# SDuino_ultramicroOLED_radio4.net
KiCad netlist of a schematic drawn in EAGLE
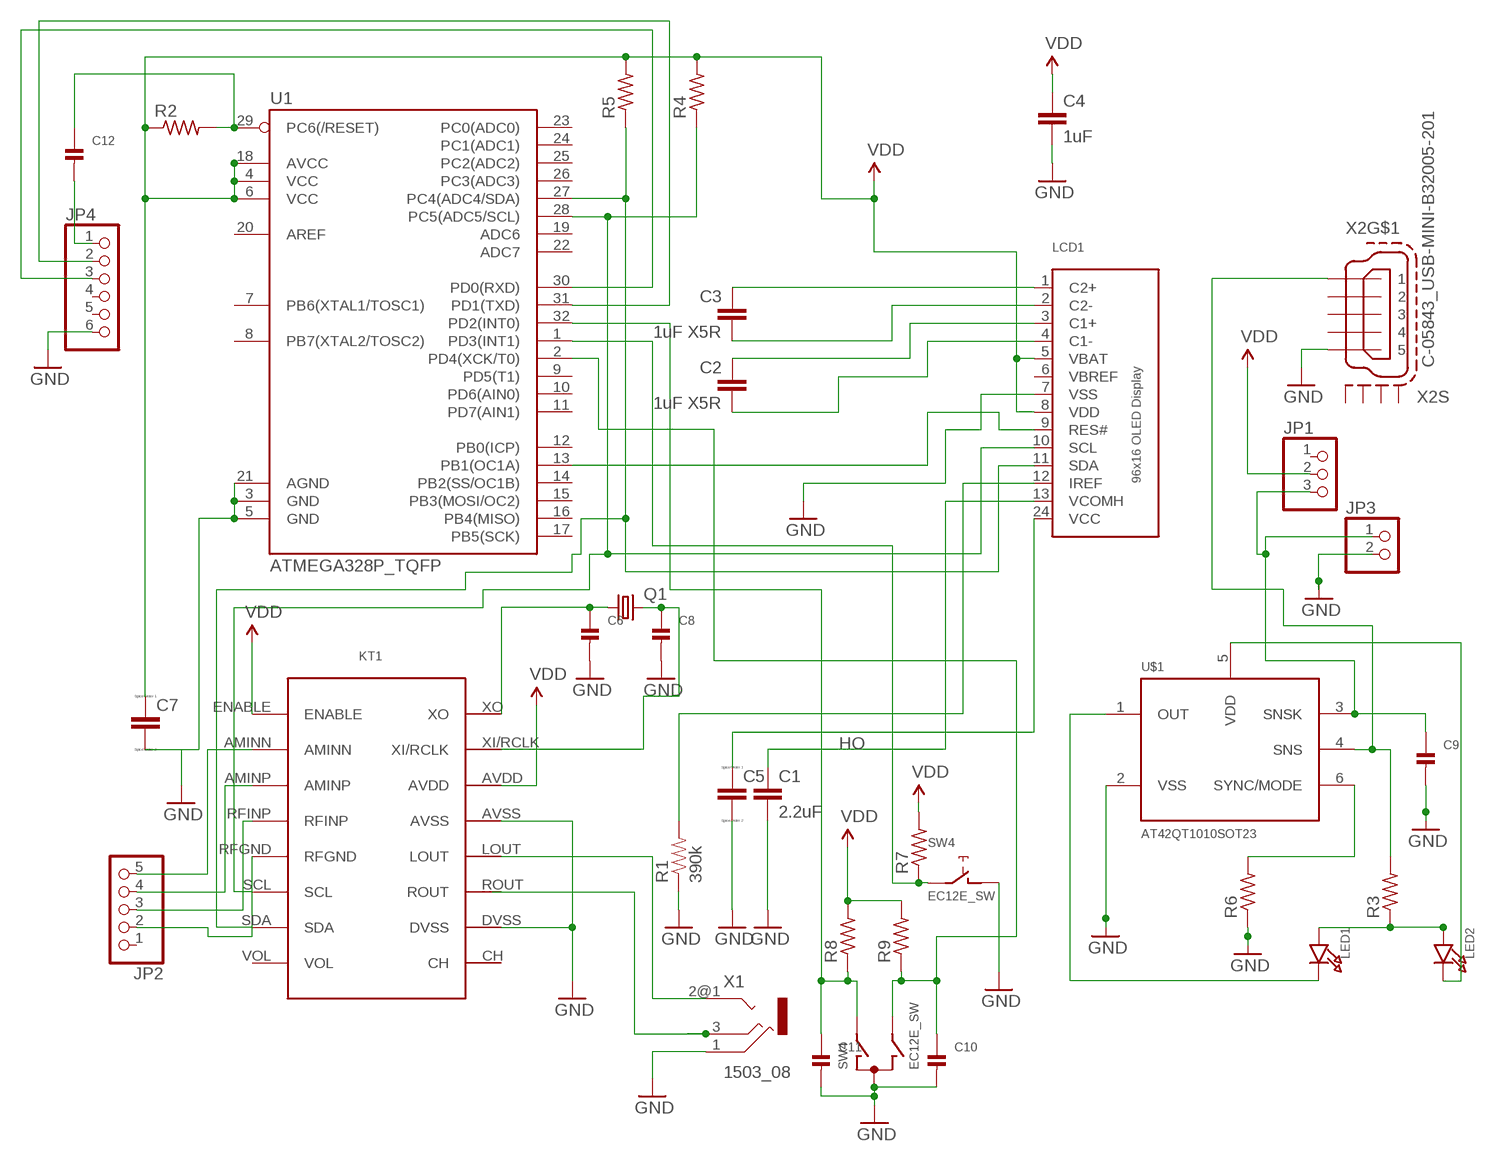
[diagram p0: schematic, sheet 1]

(export (version "E")
  (design (tool "Eeschema 10.0.6"))
  (components
    (comp (ref "C1")
      (value "2.2uF")
      (footprint "eagle-import:0805")
      (libsource (lib "eagle-import") (part "CAP0805"))
    )
    (comp (ref "C2")
      (value "1uF X5R")
      (footprint "eagle-import:0805")
      (libsource (lib "eagle-import") (part "CAP0805"))
    )
    (comp (ref "C3")
      (value "1uF X5R")
      (footprint "eagle-import:0805")
      (libsource (lib "eagle-import") (part "CAP0805"))
    )
    (comp (ref "C4")
      (value "1uF")
      (footprint "eagle-import:0603-CAP")
      (libsource (lib "eagle-import") (part "CAP0603-CAP"))
    )
    (comp (ref "C5")
      (value "CC0603")
      (footprint "eagle-import:C0603")
      (libsource (lib "eagle-import") (part "CC0603"))
    )
    (comp (ref "C6")
      (value "CAP_CERAMIC0603")
      (footprint "eagle-import:0603")
      (libsource (lib "eagle-import") (part "CAP_CERAMIC0603"))
    )
    (comp (ref "C7")
      (value "CC0603")
      (footprint "eagle-import:C0603")
      (libsource (lib "eagle-import") (part "CC0603"))
    )
    (comp (ref "C8")
      (value "CAP_CERAMIC0603")
      (footprint "eagle-import:0603")
      (libsource (lib "eagle-import") (part "CAP_CERAMIC0603"))
    )
    (comp (ref "C9")
      (value "CAP_CERAMIC0603")
      (footprint "eagle-import:0603")
      (libsource (lib "eagle-import") (part "CAP_CERAMIC0603"))
    )
    (comp (ref "C10")
      (value "CAP_CERAMIC0603")
      (footprint "eagle-import:0603")
      (libsource (lib "eagle-import") (part "CAP_CERAMIC0603"))
    )
    (comp (ref "C11")
      (value "CAP_CERAMIC0603")
      (footprint "eagle-import:0603")
      (libsource (lib "eagle-import") (part "CAP_CERAMIC0603"))
    )
    (comp (ref "C12")
      (value "CAP_CERAMIC0603")
      (footprint "eagle-import:0603")
      (libsource (lib "eagle-import") (part "CAP_CERAMIC0603"))
    )
    (comp (ref "JP1")
      (value "HEADER-1X3")
      (footprint "eagle-import:1X03_OVAL")
      (libsource (lib "eagle-import") (part "HEADER-1X3"))
    )
    (comp (ref "JP2")
      (value "HEADER-1X5")
      (footprint "eagle-import:1X05_OVAL")
      (libsource (lib "eagle-import") (part "HEADER-1X5"))
    )
    (comp (ref "JP3")
      (value "HEADER-1X2")
      (footprint "eagle-import:1X02_OVAL")
      (libsource (lib "eagle-import") (part "HEADER-1X2"))
    )
    (comp (ref "JP4")
      (value "HEADER-1X6")
      (footprint "eagle-import:1X06_OVAL")
      (libsource (lib "eagle-import") (part "HEADER-1X6"))
    )
    (comp (ref "KT1")
      (value "KT0915")
      (footprint "eagle-import:KT0915")
      (libsource (lib "eagle-import") (part "KT0915"))
    )
    (comp (ref "LCD1")
      (value "DISP_OLED_UG-9616GLBBG02")
      (footprint "eagle-import:UG-9616GLBBG02_0.65MM_WRAPAROUND")
      (libsource (lib "eagle-import") (part "DISP_OLED_UG-9616GLBBG02"))
    )
    (comp (ref "LED1")
      (value "LED0603")
      (footprint "eagle-import:CHIPLED_0603")
      (libsource (lib "eagle-import") (part "LED0603"))
    )
    (comp (ref "LED2")
      (value "LED0603")
      (footprint "eagle-import:CHIPLED_0603")
      (libsource (lib "eagle-import") (part "LED0603"))
    )
    (comp (ref "Q1")
      (value "CRYSTALTC26V")
      (footprint "eagle-import:TC26V")
      (libsource (lib "eagle-import") (part "CRYSTALTC26V"))
    )
    (comp (ref "R1")
      (value "390k")
      (footprint "eagle-import:0603-RES")
      (libsource (lib "eagle-import") (part "RESISTOR0603-RES"))
    )
    (comp (ref "R2")
      (value "R-US_R0603")
      (footprint "eagle-import:R0603")
      (libsource (lib "eagle-import") (part "R-US_R0603"))
    )
    (comp (ref "R3")
      (value "R-US_R0603")
      (footprint "eagle-import:R0603")
      (libsource (lib "eagle-import") (part "R-US_R0603"))
    )
    (comp (ref "R4")
      (value "R-US_R0603")
      (footprint "eagle-import:R0603")
      (libsource (lib "eagle-import") (part "R-US_R0603"))
    )
    (comp (ref "R5")
      (value "R-US_R0603")
      (footprint "eagle-import:R0603")
      (libsource (lib "eagle-import") (part "R-US_R0603"))
    )
    (comp (ref "R6")
      (value "R-US_R0603")
      (footprint "eagle-import:R0603")
      (libsource (lib "eagle-import") (part "R-US_R0603"))
    )
    (comp (ref "R7")
      (value "R-US_R0603")
      (footprint "eagle-import:R0603")
      (libsource (lib "eagle-import") (part "R-US_R0603"))
    )
    (comp (ref "R8")
      (value "R-US_R0603")
      (footprint "eagle-import:R0603")
      (libsource (lib "eagle-import") (part "R-US_R0603"))
    )
    (comp (ref "R9")
      (value "R-US_R0603")
      (footprint "eagle-import:R0603")
      (libsource (lib "eagle-import") (part "R-US_R0603"))
    )
    (comp (ref "SW4")
      (value "EC12E_SW")
      (footprint "eagle-import:ALPS_EC12E_SW")
      (fields (field (name "MPN") "EC12E2424407"))
      (libsource (lib "eagle-import") (part "EC12E_SW"))
    )
    (comp (ref "U$1")
      (value "AT42QT1010SOT23")
      (footprint "eagle-import:SOT23-6")
      (libsource (lib "eagle-import") (part "AT42QT1010SOT23"))
    )
    (comp (ref "U1")
      (value "ATMEGA328P_TQFP")
      (footprint "eagle-import:TQFP32-08")
      (libsource (lib "eagle-import") (part "ATMEGA328P_TQFP"))
    )
    (comp (ref "X1")
      (value "1503_08")
      (footprint "eagle-import:1503_08")
      (libsource (lib "eagle-import") (part "1503_?08"))
    )
    (comp (ref "X2")
      (value "C-05843_USB-MINI-B32005-201")
      (footprint "eagle-import:32005-201")
      (libsource (lib "eagle-import") (part "C-05843_USB-MINI-B32005-201"))
    )
  )
  (nets
    (net (code "1") (name "/HO") (class "Default")
      (node (ref "C1") (pin "1") (pinfunction "1_1") (pintype "passive"))
      (node (ref "LCD1") (pin "13") (pinfunction "VCOMH_13") (pintype "bidirectional"))
    )
    (net (code "2") (name "GND") (class "Default")
      (node (ref "C1") (pin "2") (pinfunction "2_2") (pintype "passive"))
      (node (ref "C10") (pin "2") (pinfunction "P$2_2") (pintype "passive"))
      (node (ref "C11") (pin "2") (pinfunction "P$2_2") (pintype "passive"))
      (node (ref "C4") (pin "2") (pinfunction "2_2") (pintype "passive"))
      (node (ref "C5") (pin "2") (pinfunction "2_2") (pintype "passive"))
      (node (ref "C6") (pin "2") (pinfunction "P$2_2") (pintype "passive"))
      (node (ref "C7") (pin "2") (pinfunction "2_2") (pintype "passive"))
      (node (ref "C8") (pin "2") (pinfunction "P$2_2") (pintype "passive"))
      (node (ref "C9") (pin "2") (pinfunction "P$2_2") (pintype "passive"))
      (node (ref "JP3") (pin "2") (pinfunction "2_2") (pintype "passive"))
      (node (ref "JP4") (pin "6") (pinfunction "6_6") (pintype "passive"))
      (node (ref "KT1") (pin "AVSS") (pinfunction "AVSS_AVSS") (pintype "bidirectional"))
      (node (ref "KT1") (pin "DVSS") (pinfunction "DVSS_DVSS") (pintype "bidirectional"))
      (node (ref "LCD1") (pin "7") (pinfunction "VSS_7") (pintype "bidirectional"))
      (node (ref "R1") (pin "1") (pinfunction "1_1") (pintype "passive"))
      (node (ref "R6") (pin "1") (pinfunction "1_1") (pintype "passive"))
      (node (ref "SW4") (pin "C") (pinfunction "C_C") (pintype "passive"))
      (node (ref "SW4") (pin "D") (pinfunction "1_D") (pintype "passive"))
      (node (ref "U$1") (pin "2") (pinfunction "VSS_2") (pintype "bidirectional"))
      (node (ref "U1") (pin "21") (pinfunction "AGND_21") (pintype "bidirectional"))
      (node (ref "U1") (pin "3") (pinfunction "GND_3") (pintype "bidirectional"))
      (node (ref "U1") (pin "5") (pinfunction "GND_5") (pintype "bidirectional"))
      (node (ref "X1") (pin "1") (pinfunction "1_1") (pintype "passive"))
      (node (ref "X2") (pin "5") (pinfunction "5_5") (pintype "passive"))
    )
    (net (code "3") (name "Net-(C6-P$1)") (class "Default")
      (node (ref "C6") (pin "1") (pinfunction "P$1_1") (pintype "passive"))
      (node (ref "KT1") (pin "XO") (pinfunction "XO_XO") (pintype "bidirectional"))
      (node (ref "Q1") (pin "1") (pinfunction "1_1") (pintype "passive"))
    )
    (net (code "4") (name "Net-(C8-P$1)") (class "Default")
      (node (ref "C8") (pin "1") (pinfunction "P$1_1") (pintype "passive"))
      (node (ref "KT1") (pin "XI/RCLK") (pinfunction "XI/RCLK_XI/RCLK") (pintype "bidirectional"))
      (node (ref "Q1") (pin "2") (pinfunction "2_2") (pintype "passive"))
    )
    (net (code "5") (name "Net-(C9-P$1)") (class "Default")
      (node (ref "C9") (pin "1") (pinfunction "P$1_1") (pintype "passive"))
      (node (ref "JP1") (pin "3") (pinfunction "3_3") (pintype "passive"))
      (node (ref "JP3") (pin "1") (pinfunction "1_1") (pintype "passive"))
      (node (ref "U$1") (pin "3") (pinfunction "SNSK_3") (pintype "bidirectional"))
    )
    (net (code "6") (name "Net-(C10-P$1)") (class "Default")
      (node (ref "C10") (pin "1") (pinfunction "P$1_1") (pintype "passive"))
      (node (ref "R9") (pin "1") (pinfunction "1_1") (pintype "passive"))
      (node (ref "SW4") (pin "B") (pinfunction "B_B") (pintype "passive"))
      (node (ref "U1") (pin "2") (pinfunction "PD4(XCK/T0)_2") (pintype "bidirectional"))
    )
    (net (code "7") (name "Net-(C11-P$1)") (class "Default")
      (node (ref "C11") (pin "1") (pinfunction "P$1_1") (pintype "passive"))
      (node (ref "R8") (pin "1") (pinfunction "1_1") (pintype "passive"))
      (node (ref "SW4") (pin "A") (pinfunction "A_A") (pintype "passive"))
      (node (ref "U1") (pin "32") (pinfunction "PD2(INT0)_32") (pintype "bidirectional"))
    )
    (net (code "8") (name "Net-(C12-P$1)") (class "Default")
      (node (ref "C12") (pin "1") (pinfunction "P$1_1") (pintype "passive"))
      (node (ref "R2") (pin "2") (pinfunction "2_2") (pintype "passive"))
      (node (ref "U1") (pin "29") (pinfunction "PC6(/RESET)_29") (pintype "bidirectional"))
    )
    (net (code "9") (name "Net-(C12-P$2)") (class "Default")
      (node (ref "C12") (pin "2") (pinfunction "P$2_2") (pintype "passive"))
      (node (ref "JP4") (pin "1") (pinfunction "1_1") (pintype "passive"))
    )
    (net (code "10") (name "Net-(JP2-Pad2)") (class "Default")
      (node (ref "JP2") (pin "2") (pinfunction "2_2") (pintype "passive"))
      (node (ref "KT1") (pin "RFGND") (pinfunction "RFGND_RFGND") (pintype "bidirectional"))
    )
    (net (code "11") (name "Net-(JP2-Pad3)") (class "Default")
      (node (ref "JP2") (pin "3") (pinfunction "3_3") (pintype "passive"))
      (node (ref "KT1") (pin "RFINP") (pinfunction "RFINP_RFINP") (pintype "bidirectional"))
    )
    (net (code "12") (name "Net-(JP2-Pad4)") (class "Default")
      (node (ref "JP2") (pin "4") (pinfunction "4_4") (pintype "passive"))
      (node (ref "KT1") (pin "AMINP") (pinfunction "AMINP_AMINP") (pintype "bidirectional"))
    )
    (net (code "13") (name "Net-(JP2-Pad5)") (class "Default")
      (node (ref "JP2") (pin "5") (pinfunction "5_5") (pintype "passive"))
      (node (ref "KT1") (pin "AMINN") (pinfunction "AMINN_AMINN") (pintype "bidirectional"))
    )
    (net (code "14") (name "Net-(KT1-PadLOUT)") (class "Default")
      (node (ref "KT1") (pin "LOUT") (pinfunction "LOUT_LOUT") (pintype "bidirectional"))
      (node (ref "X1") (pin "2@1") (pinfunction "2_2@1") (pintype "passive"))
    )
    (net (code "15") (name "Net-(KT1-PadROUT)") (class "Default")
      (node (ref "KT1") (pin "ROUT") (pinfunction "ROUT_ROUT") (pintype "bidirectional"))
      (node (ref "X1") (pin "3") (pinfunction "3_3") (pintype "passive"))
    )
    (net (code "16") (name "Net-(LCD1-C1+)") (class "Default")
      (node (ref "C2") (pin "1") (pinfunction "1_1") (pintype "passive"))
      (node (ref "LCD1") (pin "3") (pinfunction "C1+_3") (pintype "bidirectional"))
    )
    (net (code "17") (name "Net-(LCD1-C1-)") (class "Default")
      (node (ref "C2") (pin "2") (pinfunction "2_2") (pintype "passive"))
      (node (ref "LCD1") (pin "4") (pinfunction "C1-_4") (pintype "bidirectional"))
    )
    (net (code "18") (name "Net-(LCD1-C2+)") (class "Default")
      (node (ref "C3") (pin "1") (pinfunction "1_1") (pintype "passive"))
      (node (ref "LCD1") (pin "1") (pinfunction "C2+_1") (pintype "bidirectional"))
    )
    (net (code "19") (name "Net-(LCD1-C2-)") (class "Default")
      (node (ref "C3") (pin "2") (pinfunction "2_2") (pintype "passive"))
      (node (ref "LCD1") (pin "2") (pinfunction "C2-_2") (pintype "bidirectional"))
    )
    (net (code "20") (name "Net-(LCD1-IREF)") (class "Default")
      (node (ref "LCD1") (pin "12") (pinfunction "IREF_12") (pintype "bidirectional"))
      (node (ref "R1") (pin "2") (pinfunction "2_2") (pintype "passive"))
    )
    (net (code "21") (name "Net-(LCD1-RES#)") (class "Default")
      (node (ref "LCD1") (pin "9") (pinfunction "RES#_9") (pintype "bidirectional"))
      (node (ref "U1") (pin "13") (pinfunction "PB1(OC1A)_13") (pintype "bidirectional"))
    )
    (net (code "22") (name "Net-(LCD1-SCL)") (class "Default")
      (node (ref "KT1") (pin "SCL") (pinfunction "SCL_SCL") (pintype "bidirectional"))
      (node (ref "LCD1") (pin "10") (pinfunction "SCL_10") (pintype "bidirectional"))
      (node (ref "R4") (pin "1") (pinfunction "1_1") (pintype "passive"))
      (node (ref "U1") (pin "28") (pinfunction "PC5(ADC5/SCL)_28") (pintype "bidirectional"))
    )
    (net (code "23") (name "Net-(LCD1-SDA)") (class "Default")
      (node (ref "KT1") (pin "SDA") (pinfunction "SDA_SDA") (pintype "bidirectional"))
      (node (ref "LCD1") (pin "11") (pinfunction "SDA_11") (pintype "bidirectional"))
      (node (ref "R5") (pin "1") (pinfunction "1_1") (pintype "passive"))
      (node (ref "U1") (pin "27") (pinfunction "PC4(ADC4/SDA)_27") (pintype "bidirectional"))
    )
    (net (code "24") (name "Net-(LCD1-VCC)") (class "Default")
      (node (ref "C5") (pin "1") (pinfunction "1_1") (pintype "passive"))
      (node (ref "LCD1") (pin "24") (pinfunction "VCC_24") (pintype "bidirectional"))
    )
    (net (code "25") (name "Net-(LED1-PadA)") (class "Default")
      (node (ref "LED1") (pin "A") (pinfunction "A_A") (pintype "passive"))
      (node (ref "LED2") (pin "A") (pinfunction "A_A") (pintype "passive"))
      (node (ref "R3") (pin "1") (pinfunction "1_1") (pintype "passive"))
    )
    (net (code "26") (name "Net-(SW4B-2)") (class "Default")
      (node (ref "R7") (pin "1") (pinfunction "1_1") (pintype "passive"))
      (node (ref "SW4") (pin "E") (pinfunction "2_E") (pintype "passive"))
      (node (ref "U1") (pin "1") (pinfunction "PD3(INT1)_1") (pintype "bidirectional"))
    )
    (net (code "27") (name "Net-(U$1-OUT)") (class "Default")
      (node (ref "LED1") (pin "C") (pinfunction "C_C") (pintype "passive"))
      (node (ref "U$1") (pin "1") (pinfunction "OUT_1") (pintype "bidirectional"))
    )
    (net (code "28") (name "Net-(U$1-SNS)") (class "Default")
      (node (ref "R3") (pin "2") (pinfunction "2_2") (pintype "passive"))
      (node (ref "U$1") (pin "4") (pinfunction "SNS_4") (pintype "bidirectional"))
      (node (ref "X2") (pin "1") (pinfunction "1_1") (pintype "passive"))
    )
    (net (code "29") (name "Net-(U$1-SYNC{slash}MODE)") (class "Default")
      (node (ref "R6") (pin "2") (pinfunction "2_2") (pintype "passive"))
      (node (ref "U$1") (pin "6") (pinfunction "SYNC/MODE_6") (pintype "bidirectional"))
    )
    (net (code "30") (name "Net-(U$1-VDD)") (class "Default")
      (node (ref "LED2") (pin "C") (pinfunction "C_C") (pintype "passive"))
      (node (ref "U$1") (pin "5") (pinfunction "VDD_5") (pintype "bidirectional"))
    )
    (net (code "31") (name "Net-(U1-PD0(RXD))") (class "Default")
      (node (ref "JP4") (pin "3") (pinfunction "3_3") (pintype "passive"))
      (node (ref "U1") (pin "30") (pinfunction "PD0(RXD)_30") (pintype "bidirectional"))
    )
    (net (code "32") (name "Net-(U1-PD1(TXD))") (class "Default")
      (node (ref "JP4") (pin "2") (pinfunction "2_2") (pintype "passive"))
      (node (ref "U1") (pin "31") (pinfunction "PD1(TXD)_31") (pintype "bidirectional"))
    )
    (net (code "33") (name "VDD") (class "Default")
      (node (ref "C4") (pin "1") (pinfunction "1_1") (pintype "passive"))
      (node (ref "C7") (pin "1") (pinfunction "1_1") (pintype "passive"))
      (node (ref "JP1") (pin "2") (pinfunction "2_2") (pintype "passive"))
      (node (ref "KT1") (pin "AVDD") (pinfunction "AVDD_AVDD") (pintype "bidirectional"))
      (node (ref "KT1") (pin "ENABLE") (pinfunction "ENABLE_ENABLE") (pintype "bidirectional"))
      (node (ref "LCD1") (pin "5") (pinfunction "VBAT_5") (pintype "bidirectional"))
      (node (ref "LCD1") (pin "8") (pinfunction "VDD_8") (pintype "bidirectional"))
      (node (ref "R2") (pin "1") (pinfunction "1_1") (pintype "passive"))
      (node (ref "R4") (pin "2") (pinfunction "2_2") (pintype "passive"))
      (node (ref "R5") (pin "2") (pinfunction "2_2") (pintype "passive"))
      (node (ref "R7") (pin "2") (pinfunction "2_2") (pintype "passive"))
      (node (ref "R8") (pin "2") (pinfunction "2_2") (pintype "passive"))
      (node (ref "R9") (pin "2") (pinfunction "2_2") (pintype "passive"))
      (node (ref "U1") (pin "18") (pinfunction "AVCC_18") (pintype "bidirectional"))
      (node (ref "U1") (pin "4") (pinfunction "VCC_4") (pintype "bidirectional"))
      (node (ref "U1") (pin "6") (pinfunction "VCC_6") (pintype "bidirectional"))
    )
    (net (code "34") (name "unconnected-(JP1-Pad1)") (class "Default")
      (node (ref "JP1") (pin "1") (pinfunction "1_1") (pintype "passive"))
    )
    (net (code "35") (name "unconnected-(JP2-Pad1)") (class "Default")
      (node (ref "JP2") (pin "1") (pinfunction "1_1") (pintype "passive"))
    )
    (net (code "36") (name "unconnected-(JP4-Pad4)") (class "Default")
      (node (ref "JP4") (pin "4") (pinfunction "4_4") (pintype "passive"))
    )
    (net (code "37") (name "unconnected-(JP4-Pad5)") (class "Default")
      (node (ref "JP4") (pin "5") (pinfunction "5_5") (pintype "passive"))
    )
    (net (code "38") (name "unconnected-(KT1-PadCH)") (class "Default")
      (node (ref "KT1") (pin "CH") (pinfunction "CH_CH") (pintype "bidirectional"))
    )
    (net (code "39") (name "unconnected-(KT1-PadVOL)") (class "Default")
      (node (ref "KT1") (pin "VOL") (pinfunction "VOL_VOL") (pintype "bidirectional"))
    )
    (net (code "40") (name "unconnected-(LCD1-VBREF-Pad6)") (class "Default")
      (node (ref "LCD1") (pin "6") (pinfunction "VBREF_6") (pintype "bidirectional"))
    )
    (net (code "41") (name "unconnected-(U1-ADC6-Pad19)") (class "Default")
      (node (ref "U1") (pin "19") (pinfunction "ADC6_19") (pintype "bidirectional"))
    )
    (net (code "42") (name "unconnected-(U1-ADC7-Pad22)") (class "Default")
      (node (ref "U1") (pin "22") (pinfunction "ADC7_22") (pintype "bidirectional"))
    )
    (net (code "43") (name "unconnected-(U1-AREF-Pad20)") (class "Default")
      (node (ref "U1") (pin "20") (pinfunction "AREF_20") (pintype "bidirectional"))
    )
    (net (code "44") (name "unconnected-(U1-PB0(ICP)-Pad12)") (class "Default")
      (node (ref "U1") (pin "12") (pinfunction "PB0(ICP)_12") (pintype "bidirectional"))
    )
    (net (code "45") (name "unconnected-(U1-PB2(SS{slash}OC1B)-Pad14)") (class "Default")
      (node (ref "U1") (pin "14") (pinfunction "PB2(SS/OC1B)_14") (pintype "bidirectional"))
    )
    (net (code "46") (name "unconnected-(U1-PB3(MOSI{slash}OC2)-Pad15)") (class "Default")
      (node (ref "U1") (pin "15") (pinfunction "PB3(MOSI/OC2)_15") (pintype "bidirectional"))
    )
    (net (code "47") (name "unconnected-(U1-PB4(MISO)-Pad16)") (class "Default")
      (node (ref "U1") (pin "16") (pinfunction "PB4(MISO)_16") (pintype "bidirectional"))
    )
    (net (code "48") (name "unconnected-(U1-PB5(SCK)-Pad17)") (class "Default")
      (node (ref "U1") (pin "17") (pinfunction "PB5(SCK)_17") (pintype "bidirectional"))
    )
    (net (code "49") (name "unconnected-(U1-PB6(XTAL1{slash}TOSC1)-Pad7)") (class "Default")
      (node (ref "U1") (pin "7") (pinfunction "PB6(XTAL1/TOSC1)_7") (pintype "bidirectional"))
    )
    (net (code "50") (name "unconnected-(U1-PB7(XTAL2{slash}TOSC2)-Pad8)") (class "Default")
      (node (ref "U1") (pin "8") (pinfunction "PB7(XTAL2/TOSC2)_8") (pintype "bidirectional"))
    )
    (net (code "51") (name "unconnected-(U1-PC0(ADC0)-Pad23)") (class "Default")
      (node (ref "U1") (pin "23") (pinfunction "PC0(ADC0)_23") (pintype "bidirectional"))
    )
    (net (code "52") (name "unconnected-(U1-PC1(ADC1)-Pad24)") (class "Default")
      (node (ref "U1") (pin "24") (pinfunction "PC1(ADC1)_24") (pintype "bidirectional"))
    )
    (net (code "53") (name "unconnected-(U1-PC2(ADC2)-Pad25)") (class "Default")
      (node (ref "U1") (pin "25") (pinfunction "PC2(ADC2)_25") (pintype "bidirectional"))
    )
    (net (code "54") (name "unconnected-(U1-PC3(ADC3)-Pad26)") (class "Default")
      (node (ref "U1") (pin "26") (pinfunction "PC3(ADC3)_26") (pintype "bidirectional"))
    )
    (net (code "55") (name "unconnected-(U1-PD5(T1)-Pad9)") (class "Default")
      (node (ref "U1") (pin "9") (pinfunction "PD5(T1)_9") (pintype "bidirectional"))
    )
    (net (code "56") (name "unconnected-(U1-PD6(AIN0)-Pad10)") (class "Default")
      (node (ref "U1") (pin "10") (pinfunction "PD6(AIN0)_10") (pintype "bidirectional"))
    )
    (net (code "57") (name "unconnected-(U1-PD7(AIN1)-Pad11)") (class "Default")
      (node (ref "U1") (pin "11") (pinfunction "PD7(AIN1)_11") (pintype "bidirectional"))
    )
    (net (code "58") (name "unconnected-(X1-2-Pad2@2)") (class "Default")
      (node (ref "X1") (pin "2@2") (pinfunction "2_2@2") (pintype "passive"))
    )
    (net (code "59") (name "unconnected-(X2-Pad2)") (class "Default")
      (node (ref "X2") (pin "2") (pinfunction "2_2") (pintype "passive"))
    )
    (net (code "60") (name "unconnected-(X2-Pad3)") (class "Default")
      (node (ref "X2") (pin "3") (pinfunction "3_3") (pintype "passive"))
    )
    (net (code "61") (name "unconnected-(X2-Pad4)") (class "Default")
      (node (ref "X2") (pin "4") (pinfunction "4_4") (pintype "passive"))
    )
    (net (code "62") (name "unconnected-(X2B-S1-PadM1)") (class "Default")
      (node (ref "X2") (pin "M1") (pinfunction "S1_M1") (pintype "passive"))
    )
    (net (code "63") (name "unconnected-(X2B-S2-PadM2)") (class "Default")
      (node (ref "X2") (pin "M2") (pinfunction "S2_M2") (pintype "passive"))
    )
    (net (code "64") (name "unconnected-(X2B-S3-PadM3)") (class "Default")
      (node (ref "X2") (pin "M3") (pinfunction "S3_M3") (pintype "passive"))
    )
    (net (code "65") (name "unconnected-(X2B-S4-PadM4)") (class "Default")
      (node (ref "X2") (pin "M4") (pinfunction "S4_M4") (pintype "passive"))
    )
  )
)
